# PWR_0V9_20A.net
KiCad netlist of a schematic drawn in Altium Designer
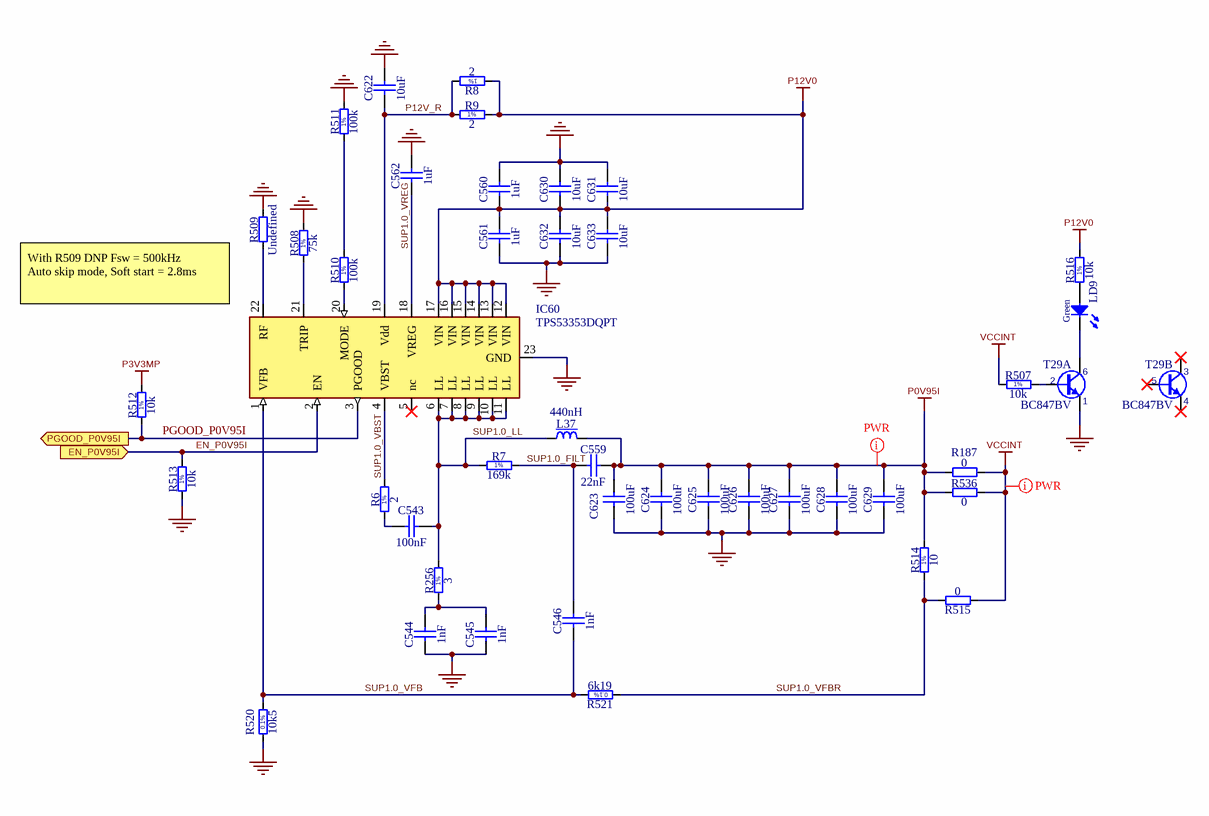
[diagram p0: PWR_0V9_20A.SchDoc]

(export (version "E")
  (design (tool "Eeschema 10.0.6"))
  (components
    (comp (ref "C543")
      (value "100nF")
      (footprint "CAPC1005X55N")
      (description "Non-polarised capacitor")
      (fields
        (field (name "MANUFACTURER PART NUMBER") "CC0402_100NF_16V_10%_X5R")
        (field (name "MANUFACTURER") "GENERIC")
        (field (name "AUTHOR") "CERN DEM JLC")
      )
      (libsource (lib "Capacitors") (part "Capacitor - non polarized"))
    )
    (comp (ref "C544")
      (value "1nF")
      (footprint "CAPC1005X55N")
      (description "Non-polarised capacitor")
      (fields
        (field (name "MANUFACTURER PART NUMBER") "CC0402_1NF_50V_10%_X7R")
        (field (name "MANUFACTURER") "GENERIC")
        (field (name "AUTHOR") "CERN DEM JLC")
      )
      (libsource (lib "Capacitors") (part "Capacitor - non polarized"))
    )
    (comp (ref "C545")
      (value "1nF")
      (footprint "CAPC1005X55N")
      (description "Non-polarised capacitor")
      (fields
        (field (name "MANUFACTURER PART NUMBER") "CC0402_1NF_50V_10%_X7R")
        (field (name "MANUFACTURER") "GENERIC")
        (field (name "AUTHOR") "CERN DEM JLC")
      )
      (libsource (lib "Capacitors") (part "Capacitor - non polarized"))
    )
    (comp (ref "C546")
      (value "1nF")
      (footprint "CAPC1005X55N")
      (description "Non-polarised capacitor")
      (fields
        (field (name "MANUFACTURER PART NUMBER") "CC0402_1NF_50V_10%_X7R")
        (field (name "MANUFACTURER") "GENERIC")
        (field (name "AUTHOR") "CERN DEM JLC")
      )
      (libsource (lib "Capacitors") (part "Capacitor - non polarized"))
    )
    (comp (ref "C559")
      (value "22nF")
      (footprint "CAPC1608X87N")
      (description "Non-polarised capacitor")
      (fields
        (field (name "MANUFACTURER PART NUMBER") "CC0603_22NF_50V_10%_X7R")
        (field (name "MANUFACTURER") "GENERIC")
        (field (name "AUTHOR") "CERN DEM JLC")
      )
      (libsource (lib "Capacitors") (part "Capacitor - non polarized"))
    )
    (comp (ref "C560")
      (value "1uF")
      (footprint "CAPC1608X87N")
      (description "Non-polarised capacitor")
      (fields
        (field (name "MANUFACTURER PART NUMBER") "CC0603_1UF_25V_10%_X7R")
        (field (name "MANUFACTURER") "GENERIC")
        (field (name "AUTHOR") "CERN DEM JLC")
      )
      (libsource (lib "Capacitors") (part "Capacitor - non polarized"))
    )
    (comp (ref "C561")
      (value "1uF")
      (footprint "CAPC1608X87N")
      (description "Non-polarised capacitor")
      (fields
        (field (name "MANUFACTURER PART NUMBER") "CC0603_1UF_25V_10%_X7R")
        (field (name "MANUFACTURER") "GENERIC")
        (field (name "AUTHOR") "CERN DEM JLC")
      )
      (libsource (lib "Capacitors") (part "Capacitor - non polarized"))
    )
    (comp (ref "C562")
      (value "1uF")
      (footprint "CAPC1608X87N")
      (description "Non-polarised capacitor")
      (fields
        (field (name "MANUFACTURER PART NUMBER") "CC0603_1UF_25V_10%_X7R")
        (field (name "MANUFACTURER") "GENERIC")
        (field (name "AUTHOR") "CERN DEM JLC")
      )
      (libsource (lib "Capacitors") (part "Capacitor - non polarized"))
    )
    (comp (ref "C622")
      (value "10uF")
      (footprint "CAPC3216X180N")
      (description "Non-polarised capacitor")
      (fields
        (field (name "MANUFACTURER PART NUMBER") "CC1206_10uF_25V_10%_X7R")
        (field (name "MANUFACTURER") "GENERIC")
        (field (name "AUTHOR") "CERN DEM JLC")
      )
      (libsource (lib "Capacitors") (part "Capacitor - non polarized"))
    )
    (comp (ref "C623")
      (value "100uF")
      (footprint "CAPC3216X180N")
      (description "Non-polarised capacitor")
      (fields
        (field (name "MANUFACTURER PART NUMBER") "CC1206_100UF_6.3V_20%_X5R")
        (field (name "MANUFACTURER") "GENERIC")
        (field (name "AUTHOR") "CERN DEM JLC")
      )
      (libsource (lib "Capacitors") (part "Capacitor - non polarized"))
    )
    (comp (ref "C624")
      (value "100uF")
      (footprint "CAPC3216X180N")
      (description "Non-polarised capacitor")
      (fields
        (field (name "MANUFACTURER PART NUMBER") "CC1206_100UF_6.3V_20%_X5R")
        (field (name "MANUFACTURER") "GENERIC")
        (field (name "AUTHOR") "CERN DEM JLC")
      )
      (libsource (lib "Capacitors") (part "Capacitor - non polarized"))
    )
    (comp (ref "C625")
      (value "100uF")
      (footprint "CAPC3216X180N")
      (description "Non-polarised capacitor")
      (fields
        (field (name "MANUFACTURER PART NUMBER") "CC1206_100UF_6.3V_20%_X5R")
        (field (name "MANUFACTURER") "GENERIC")
        (field (name "AUTHOR") "CERN DEM JLC")
      )
      (libsource (lib "Capacitors") (part "Capacitor - non polarized"))
    )
    (comp (ref "C626")
      (value "100uF")
      (footprint "CAPC3216X180N")
      (description "Non-polarised capacitor")
      (fields
        (field (name "MANUFACTURER PART NUMBER") "CC1206_100UF_6.3V_20%_X5R")
        (field (name "MANUFACTURER") "GENERIC")
        (field (name "AUTHOR") "CERN DEM JLC")
      )
      (libsource (lib "Capacitors") (part "Capacitor - non polarized"))
    )
    (comp (ref "C627")
      (value "100uF")
      (footprint "CAPC3216X180N")
      (description "Non-polarised capacitor")
      (fields
        (field (name "MANUFACTURER PART NUMBER") "CC1206_100UF_6.3V_20%_X5R")
        (field (name "MANUFACTURER") "GENERIC")
        (field (name "AUTHOR") "CERN DEM JLC")
      )
      (libsource (lib "Capacitors") (part "Capacitor - non polarized"))
    )
    (comp (ref "C628")
      (value "100uF")
      (footprint "CAPC3216X180N")
      (description "Non-polarised capacitor")
      (fields
        (field (name "MANUFACTURER PART NUMBER") "CC1206_100UF_6.3V_20%_X5R")
        (field (name "MANUFACTURER") "GENERIC")
        (field (name "AUTHOR") "CERN DEM JLC")
      )
      (libsource (lib "Capacitors") (part "Capacitor - non polarized"))
    )
    (comp (ref "C629")
      (value "100uF")
      (footprint "CAPC3216X180N")
      (description "Non-polarised capacitor")
      (fields
        (field (name "MANUFACTURER PART NUMBER") "CC1206_100UF_6.3V_20%_X5R")
        (field (name "MANUFACTURER") "GENERIC")
        (field (name "AUTHOR") "CERN DEM JLC")
      )
      (libsource (lib "Capacitors") (part "Capacitor - non polarized"))
    )
    (comp (ref "C630")
      (value "10uF")
      (footprint "CAPC3216X180N")
      (description "Non-polarised capacitor")
      (fields
        (field (name "MANUFACTURER PART NUMBER") "CC1206_10uF_25V_10%_X7R")
        (field (name "MANUFACTURER") "GENERIC")
        (field (name "AUTHOR") "CERN DEM JLC")
      )
      (libsource (lib "Capacitors") (part "Capacitor - non polarized"))
    )
    (comp (ref "C631")
      (value "10uF")
      (footprint "CAPC3216X180N")
      (description "Non-polarised capacitor")
      (fields
        (field (name "MANUFACTURER PART NUMBER") "CC1206_10uF_25V_10%_X7R")
        (field (name "MANUFACTURER") "GENERIC")
        (field (name "AUTHOR") "CERN DEM JLC")
      )
      (libsource (lib "Capacitors") (part "Capacitor - non polarized"))
    )
    (comp (ref "C632")
      (value "10uF")
      (footprint "CAPC3216X180N")
      (description "Non-polarised capacitor")
      (fields
        (field (name "MANUFACTURER PART NUMBER") "CC1206_10uF_25V_10%_X7R")
        (field (name "MANUFACTURER") "GENERIC")
        (field (name "AUTHOR") "CERN DEM JLC")
      )
      (libsource (lib "Capacitors") (part "Capacitor - non polarized"))
    )
    (comp (ref "C633")
      (value "10uF")
      (footprint "CAPC3216X180N")
      (description "Non-polarised capacitor")
      (fields
        (field (name "MANUFACTURER PART NUMBER") "CC1206_10uF_25V_10%_X7R")
        (field (name "MANUFACTURER") "GENERIC")
        (field (name "AUTHOR") "CERN DEM JLC")
      )
      (libsource (lib "Capacitors") (part "Capacitor - non polarized"))
    )
    (comp (ref "IC60")
      (value "TPS53353DQPT")
      (footprint "LCCS50P600X500X150-22N")
      (description "High-Efficiency 20-A Synchronous Buck Converter with Eco-mode™")
      (libsource (lib "LIBRARY_SCH") (part "PM_TPS53353"))
    )
    (comp (ref "L37")
      (value "440nH")
      (footprint "IND_PULSE_PA0513")
      (description "Inductor With Core")
      (fields
        (field (name "MANUFACTURER PART NUMBER") "PA0513.441NLT")
        (field (name "MANUFACTURER") "PULSE ELECTRONICS")
        (field (name "AUTHOR") "CERN DEM JLC")
      )
      (libsource (lib "Inductors & Transformers") (part "Inductor With Magnetic core"))
    )
    (comp (ref "LD9")
      (value "Green")
      (footprint "LED_KINGBRIGHT_KPH-1608CGCK")
      (description "LED Green 1C 2A")
      (fields
        (field (name "MANUFACTURER PART NUMBER") "KPH-1608CGCK")
        (field (name "MANUFACTURER") "KINGBRIGHT")
        (field (name "AUTHOR") "CERN DEM JLC")
      )
      (libsource (lib "ICs And Semiconductors") (part "LED Green 1C 2A"))
    )
    (comp (ref "R6")
      (value "2")
      (footprint "RESC1608X55N")
      (description "Resistor - 1%")
      (fields
        (field (name "MANUFACTURER PART NUMBER") "R0603_2R_1%_0.1W_200PPM")
        (field (name "MANUFACTURER") "GENERIC")
        (field (name "AUTHOR") "CERN DEM JLC")
      )
      (libsource (lib "Resistors") (part "Resistor - 1%"))
    )
    (comp (ref "R7")
      (value "169k")
      (footprint "RESC1608X55N")
      (description "Resistor - 1%")
      (fields
        (field (name "MANUFACTURER PART NUMBER") "R0603_169K_1%_0.1W_100PPM")
        (field (name "MANUFACTURER") "GENERIC")
        (field (name "AUTHOR") "CERN DEM JLC")
      )
      (libsource (lib "Resistors") (part "Resistor - 1%"))
    )
    (comp (ref "R8")
      (value "2")
      (footprint "RESC1608X55N")
      (description "Resistor - 1%")
      (fields
        (field (name "MANUFACTURER PART NUMBER") "R0603_2R_1%_0.1W_200PPM")
        (field (name "MANUFACTURER") "GENERIC")
        (field (name "AUTHOR") "CERN DEM JLC")
      )
      (libsource (lib "Resistors") (part "Resistor - 1%"))
    )
    (comp (ref "R9")
      (value "2")
      (footprint "RESC1608X55N")
      (description "Resistor - 1%")
      (fields
        (field (name "MANUFACTURER PART NUMBER") "R0603_2R_1%_0.1W_200PPM")
        (field (name "MANUFACTURER") "GENERIC")
        (field (name "AUTHOR") "CERN DEM JLC")
      )
      (libsource (lib "Resistors") (part "Resistor - 1%"))
    )
    (comp (ref "R187")
      (value "0")
      (footprint "RESC6331X70N")
      (description "Resistor")
      (fields
        (field (name "MANUFACTURER PART NUMBER") "R2512_0R_JUMPER")
        (field (name "MANUFACTURER") "GENERIC")
        (field (name "AUTHOR") "CERN DEM JLC")
      )
      (libsource (lib "Resistors") (part "Resistor"))
    )
    (comp (ref "R256")
      (value "3")
      (footprint "RESC3216X65N")
      (description "Resistor - 1%")
      (fields
        (field (name "MANUFACTURER PART NUMBER") "R1206_3R_1%_0.25W_200PPM")
        (field (name "MANUFACTURER") "GENERIC")
        (field (name "AUTHOR") "CERN DEM JLC")
      )
      (libsource (lib "Resistors") (part "Resistor - 1%"))
    )
    (comp (ref "R507")
      (value "10k")
      (footprint "RESC1005X40N")
      (description "Resistor - 1%")
      (fields
        (field (name "MANUFACTURER PART NUMBER") "R0402_10K_1%_0.0625W_100PPM")
        (field (name "MANUFACTURER") "GENERIC")
        (field (name "AUTHOR") "CERN DEM JLC")
      )
      (libsource (lib "Resistors") (part "Resistor - 1%"))
    )
    (comp (ref "R508")
      (value "75k")
      (footprint "RESC1005X40N")
      (description "Resistor - 1%")
      (fields
        (field (name "MANUFACTURER PART NUMBER") "R0402_75K_1%_0.0625W_100PPM")
        (field (name "MANUFACTURER") "GENERIC")
        (field (name "AUTHOR") "CERN DEM JLC")
      )
      (libsource (lib "Resistors") (part "Resistor - 1%"))
    )
    (comp (ref "R509")
      (value "Undefined")
      (footprint "RESC1005X40N")
      (description "Resistor")
      (fields
        (field (name "MANUFACTURER PART NUMBER") "R0402_NO-VALUE")
        (field (name "AUTHOR") "CERN DEM JLC")
      )
      (libsource (lib "Resistors") (part "Resistor"))
    )
    (comp (ref "R510")
      (value "100k")
      (footprint "RESC1005X40N")
      (description "Resistor - 1%")
      (fields
        (field (name "MANUFACTURER PART NUMBER") "R0402_100K_1%_0.0625W_100PPM")
        (field (name "MANUFACTURER") "GENERIC")
        (field (name "AUTHOR") "CERN DEM JLC")
      )
      (libsource (lib "Resistors") (part "Resistor - 1%"))
    )
    (comp (ref "R511")
      (value "100k")
      (footprint "RESC1005X40N")
      (description "Resistor - 1%")
      (fields
        (field (name "MANUFACTURER PART NUMBER") "R0402_100K_1%_0.0625W_100PPM")
        (field (name "MANUFACTURER") "GENERIC")
        (field (name "AUTHOR") "CERN DEM JLC")
      )
      (libsource (lib "Resistors") (part "Resistor - 1%"))
    )
    (comp (ref "R512")
      (value "10k")
      (footprint "RESC1005X40N")
      (description "Resistor - 1%")
      (fields
        (field (name "MANUFACTURER PART NUMBER") "R0402_10K_1%_0.0625W_100PPM")
        (field (name "MANUFACTURER") "GENERIC")
        (field (name "AUTHOR") "CERN DEM JLC")
      )
      (libsource (lib "Resistors") (part "Resistor - 1%"))
    )
    (comp (ref "R513")
      (value "10k")
      (footprint "RESC1005X40N")
      (description "Resistor - 1%")
      (fields
        (field (name "MANUFACTURER PART NUMBER") "R0402_10K_1%_0.0625W_100PPM")
        (field (name "MANUFACTURER") "GENERIC")
        (field (name "AUTHOR") "CERN DEM JLC")
      )
      (libsource (lib "Resistors") (part "Resistor - 1%"))
    )
    (comp (ref "R514")
      (value "10")
      (footprint "RESC1005X40N")
      (description "Resistor - 1%")
      (fields
        (field (name "MANUFACTURER PART NUMBER") "R0402_10R_1%_0.0625W_200PPM")
        (field (name "MANUFACTURER") "GENERIC")
        (field (name "AUTHOR") "CERN DEM JLC")
      )
      (libsource (lib "Resistors") (part "Resistor - 1%"))
    )
    (comp (ref "R515")
      (value "0")
      (footprint "RESC1005X40N")
      (description "Resistor")
      (fields
        (field (name "MANUFACTURER PART NUMBER") "R0402_0R_JUMPER")
        (field (name "MANUFACTURER") "GENERIC")
        (field (name "AUTHOR") "CERN DEM JLC")
      )
      (libsource (lib "Resistors") (part "Resistor"))
    )
    (comp (ref "R516")
      (value "10k")
      (footprint "RESC1005X40N")
      (description "Resistor - 1%")
      (fields
        (field (name "MANUFACTURER PART NUMBER") "R0402_10K_1%_0.0625W_100PPM")
        (field (name "MANUFACTURER") "GENERIC")
        (field (name "AUTHOR") "CERN DEM JLC")
      )
      (libsource (lib "Resistors") (part "Resistor - 1%"))
    )
    (comp (ref "R520")
      (value "10k5")
      (footprint "RESC1608X55N")
      (description "Resistor - 0.1%")
      (fields
        (field (name "MANUFACTURER PART NUMBER") "R0603_10K5_0.1%_0.063W_10PPM")
        (field (name "MANUFACTURER") "GENERIC")
        (field (name "AUTHOR") "CERN DEM JLC")
      )
      (libsource (lib "Resistors") (part "Resistor - 0.1%"))
    )
    (comp (ref "R521")
      (value "6k19")
      (footprint "RESC1608X55N")
      (description "Resistor - 0.1%")
      (fields
        (field (name "MANUFACTURER PART NUMBER") "R0603_6K19_0.1%_0.063W_10PPM")
        (field (name "MANUFACTURER") "GENERIC")
        (field (name "AUTHOR") "CERN DEM JLC")
      )
      (libsource (lib "Resistors") (part "Resistor - 0.1%"))
    )
    (comp (ref "R536")
      (value "0")
      (footprint "RESC6331X70N")
      (description "Resistor")
      (fields
        (field (name "MANUFACTURER PART NUMBER") "R2512_0R_JUMPER")
        (field (name "MANUFACTURER") "GENERIC")
        (field (name "AUTHOR") "CERN DEM JLC")
      )
      (libsource (lib "Resistors") (part "Resistor"))
    )
    (comp (ref "T29")
      (value "BC847BV")
      (footprint "SOTFL50P160X60-6N")
      (description "45V, 100mA NPN General Purpose Double Transistor")
      (fields (field (name "MANUFACTURER") "NXP SEMICONDUCTORS") (field (name "AUTHOR") "CERN DEM JLC"))
      (libsource (lib "ICs And Semiconductors") (part "BC847BV"))
    )
  )
  (nets
    (net (code "1") (name "/EN_P0V95I") (class "Default")
      (node (ref "IC60") (pin "2") (pinfunction "EN_2") (pintype "input"))
      (node (ref "R513") (pin "2") (pinfunction "2_2") (pintype "passive"))
    )
    (net (code "2") (name "/P12V_R") (class "Default")
      (node (ref "C622") (pin "1") (pinfunction "1_1") (pintype "passive"))
      (node (ref "IC60") (pin "19") (pinfunction "Vdd_19") (pintype "power_in"))
      (node (ref "R8") (pin "1") (pinfunction "1_1") (pintype "passive"))
      (node (ref "R9") (pin "1") (pinfunction "1_1") (pintype "passive"))
    )
    (net (code "3") (name "/PGOOD_P0V95I") (class "Default")
      (node (ref "IC60") (pin "3") (pinfunction "PGOOD_3") (pintype "output"))
      (node (ref "R512") (pin "1") (pinfunction "1_1") (pintype "passive"))
    )
    (net (code "4") (name "/SUP1.0_FILT") (class "Default")
      (node (ref "C546") (pin "2") (pinfunction "2_2") (pintype "passive"))
      (node (ref "C559") (pin "1") (pinfunction "1_1") (pintype "passive"))
      (node (ref "R7") (pin "2") (pinfunction "2_2") (pintype "passive"))
    )
    (net (code "5") (name "/SUP1.0_LL") (class "Default")
      (node (ref "C543") (pin "2") (pinfunction "2_2") (pintype "passive"))
      (node (ref "IC60") (pin "10") (pinfunction "LL_10") (pintype "passive"))
      (node (ref "IC60") (pin "11") (pinfunction "LL_11") (pintype "passive"))
      (node (ref "IC60") (pin "6") (pinfunction "LL_6") (pintype "passive"))
      (node (ref "IC60") (pin "7") (pinfunction "LL_7") (pintype "passive"))
      (node (ref "IC60") (pin "8") (pinfunction "LL_8") (pintype "passive"))
      (node (ref "IC60") (pin "9") (pinfunction "LL_9") (pintype "passive"))
      (node (ref "L37") (pin "1") (pinfunction "1_1") (pintype "passive"))
      (node (ref "R256") (pin "2") (pinfunction "2_2") (pintype "passive"))
      (node (ref "R7") (pin "1") (pinfunction "1_1") (pintype "passive"))
    )
    (net (code "6") (name "/SUP1.0_VBST") (class "Default")
      (node (ref "IC60") (pin "4") (pinfunction "VBST_4") (pintype "passive"))
      (node (ref "R6") (pin "2") (pinfunction "2_2") (pintype "passive"))
    )
    (net (code "7") (name "/SUP1.0_VFB") (class "Default")
      (node (ref "C546") (pin "1") (pinfunction "1_1") (pintype "passive"))
      (node (ref "IC60") (pin "1") (pinfunction "VFB_1") (pintype "input"))
      (node (ref "R520") (pin "2") (pinfunction "2_2") (pintype "passive"))
      (node (ref "R521") (pin "2") (pinfunction "2_2") (pintype "passive"))
    )
    (net (code "8") (name "/SUP1.0_VFBR") (class "Default")
      (node (ref "R514") (pin "1") (pinfunction "1_1") (pintype "passive"))
      (node (ref "R515") (pin "2") (pinfunction "2_2") (pintype "passive"))
      (node (ref "R521") (pin "1") (pinfunction "1_1") (pintype "passive"))
    )
    (net (code "9") (name "/SUP1.0_VREG") (class "Default")
      (node (ref "C562") (pin "1") (pinfunction "1_1") (pintype "passive"))
      (node (ref "IC60") (pin "18") (pinfunction "VREG_18") (pintype "power_in"))
    )
    (net (code "10") (name "GND") (class "Default")
      (node (ref "C544") (pin "1") (pinfunction "1_1") (pintype "passive"))
      (node (ref "C545") (pin "1") (pinfunction "1_1") (pintype "passive"))
      (node (ref "C560") (pin "2") (pinfunction "2_2") (pintype "passive"))
      (node (ref "C561") (pin "1") (pinfunction "1_1") (pintype "passive"))
      (node (ref "C562") (pin "2") (pinfunction "2_2") (pintype "passive"))
      (node (ref "C622") (pin "2") (pinfunction "2_2") (pintype "passive"))
      (node (ref "C623") (pin "1") (pinfunction "1_1") (pintype "passive"))
      (node (ref "C624") (pin "1") (pinfunction "1_1") (pintype "passive"))
      (node (ref "C625") (pin "1") (pinfunction "1_1") (pintype "passive"))
      (node (ref "C626") (pin "1") (pinfunction "1_1") (pintype "passive"))
      (node (ref "C627") (pin "1") (pinfunction "1_1") (pintype "passive"))
      (node (ref "C628") (pin "1") (pinfunction "1_1") (pintype "passive"))
      (node (ref "C629") (pin "1") (pinfunction "1_1") (pintype "passive"))
      (node (ref "C630") (pin "2") (pinfunction "2_2") (pintype "passive"))
      (node (ref "C631") (pin "2") (pinfunction "2_2") (pintype "passive"))
      (node (ref "C632") (pin "1") (pinfunction "1_1") (pintype "passive"))
      (node (ref "C633") (pin "1") (pinfunction "1_1") (pintype "passive"))
      (node (ref "IC60") (pin "23") (pinfunction "GND_23") (pintype "power_in"))
      (node (ref "R508") (pin "2") (pinfunction "2_2") (pintype "passive"))
      (node (ref "R509") (pin "2") (pinfunction "2_2") (pintype "passive"))
      (node (ref "R511") (pin "2") (pinfunction "2_2") (pintype "passive"))
      (node (ref "R513") (pin "1") (pinfunction "1_1") (pintype "passive"))
      (node (ref "R520") (pin "1") (pinfunction "1_1") (pintype "passive"))
      (node (ref "T29") (pin "1") (pinfunction "E_1") (pintype "passive"))
    )
    (net (code "11") (name "Net-(C543-Pad1)") (class "Default")
      (node (ref "C543") (pin "1") (pinfunction "1_1") (pintype "passive"))
      (node (ref "R6") (pin "1") (pinfunction "1_1") (pintype "passive"))
    )
    (net (code "12") (name "Net-(C544-Pad2)") (class "Default")
      (node (ref "C544") (pin "2") (pinfunction "2_2") (pintype "passive"))
      (node (ref "C545") (pin "2") (pinfunction "2_2") (pintype "passive"))
      (node (ref "R256") (pin "1") (pinfunction "1_1") (pintype "passive"))
    )
    (net (code "13") (name "Net-(IC60-MODE)") (class "Default")
      (node (ref "IC60") (pin "20") (pinfunction "MODE_20") (pintype "input"))
      (node (ref "R510") (pin "1") (pinfunction "1_1") (pintype "passive"))
    )
    (net (code "14") (name "Net-(IC60-RF)") (class "Default")
      (node (ref "IC60") (pin "22") (pinfunction "RF_22") (pintype "passive"))
      (node (ref "R509") (pin "1") (pinfunction "1_1") (pintype "passive"))
    )
    (net (code "15") (name "Net-(IC60-TRIP)") (class "Default")
      (node (ref "IC60") (pin "21") (pinfunction "TRIP_21") (pintype "passive"))
      (node (ref "R508") (pin "1") (pinfunction "1_1") (pintype "passive"))
    )
    (net (code "16") (name "Net-(LD9-A)") (class "Default")
      (node (ref "LD9") (pin "2") (pinfunction "A_2") (pintype "passive"))
      (node (ref "R516") (pin "1") (pinfunction "1_1") (pintype "passive"))
    )
    (net (code "17") (name "Net-(LD9-C)") (class "Default")
      (node (ref "LD9") (pin "1") (pinfunction "C_1") (pintype "passive"))
      (node (ref "T29") (pin "6") (pinfunction "C_6") (pintype "passive"))
    )
    (net (code "18") (name "Net-(R510-Pad2)") (class "Default")
      (node (ref "R510") (pin "2") (pinfunction "2_2") (pintype "passive"))
      (node (ref "R511") (pin "1") (pinfunction "1_1") (pintype "passive"))
    )
    (net (code "19") (name "Net-(T29A-B)") (class "Default")
      (node (ref "R507") (pin "2") (pinfunction "2_2") (pintype "passive"))
      (node (ref "T29") (pin "2") (pinfunction "B_2") (pintype "passive"))
    )
    (net (code "20") (name "P0V95I") (class "Default")
      (node (ref "C559") (pin "2") (pinfunction "2_2") (pintype "passive"))
      (node (ref "C623") (pin "2") (pinfunction "2_2") (pintype "passive"))
      (node (ref "C624") (pin "2") (pinfunction "2_2") (pintype "passive"))
      (node (ref "C625") (pin "2") (pinfunction "2_2") (pintype "passive"))
      (node (ref "C626") (pin "2") (pinfunction "2_2") (pintype "passive"))
      (node (ref "C627") (pin "2") (pinfunction "2_2") (pintype "passive"))
      (node (ref "C628") (pin "2") (pinfunction "2_2") (pintype "passive"))
      (node (ref "C629") (pin "2") (pinfunction "2_2") (pintype "passive"))
      (node (ref "L37") (pin "2") (pinfunction "2_2") (pintype "passive"))
      (node (ref "R187") (pin "1") (pinfunction "1_1") (pintype "passive"))
      (node (ref "R514") (pin "2") (pinfunction "2_2") (pintype "passive"))
      (node (ref "R536") (pin "1") (pinfunction "1_1") (pintype "passive"))
    )
    (net (code "21") (name "P3V3MP") (class "Default")
      (node (ref "R512") (pin "2") (pinfunction "2_2") (pintype "passive"))
    )
    (net (code "22") (name "P12V0") (class "Default")
      (node (ref "C560") (pin "1") (pinfunction "1_1") (pintype "passive"))
      (node (ref "C561") (pin "2") (pinfunction "2_2") (pintype "passive"))
      (node (ref "C630") (pin "1") (pinfunction "1_1") (pintype "passive"))
      (node (ref "C631") (pin "1") (pinfunction "1_1") (pintype "passive"))
      (node (ref "C632") (pin "2") (pinfunction "2_2") (pintype "passive"))
      (node (ref "C633") (pin "2") (pinfunction "2_2") (pintype "passive"))
      (node (ref "IC60") (pin "12") (pinfunction "VIN_12") (pintype "power_in"))
      (node (ref "IC60") (pin "13") (pinfunction "VIN_13") (pintype "power_in"))
      (node (ref "IC60") (pin "14") (pinfunction "VIN_14") (pintype "power_in"))
      (node (ref "IC60") (pin "15") (pinfunction "VIN_15") (pintype "power_in"))
      (node (ref "IC60") (pin "16") (pinfunction "VIN_16") (pintype "power_in"))
      (node (ref "IC60") (pin "17") (pinfunction "VIN_17") (pintype "power_in"))
      (node (ref "R516") (pin "2") (pinfunction "2_2") (pintype "passive"))
      (node (ref "R8") (pin "2") (pinfunction "2_2") (pintype "passive"))
      (node (ref "R9") (pin "2") (pinfunction "2_2") (pintype "passive"))
    )
    (net (code "23") (name "VCCINT") (class "Default")
      (node (ref "R187") (pin "2") (pinfunction "2_2") (pintype "passive"))
      (node (ref "R507") (pin "1") (pinfunction "1_1") (pintype "passive"))
      (node (ref "R515") (pin "1") (pinfunction "1_1") (pintype "passive"))
      (node (ref "R536") (pin "2") (pinfunction "2_2") (pintype "passive"))
    )
    (net (code "24") (name "unconnected-(IC60-nc-Pad5)") (class "Default")
      (node (ref "IC60") (pin "5") (pinfunction "nc_5") (pintype "passive+no_connect"))
    )
    (net (code "25") (name "unconnected-(T29B-B-Pad5)") (class "Default")
      (node (ref "T29") (pin "5") (pinfunction "B_5") (pintype "passive+no_connect"))
    )
    (net (code "26") (name "unconnected-(T29B-C-Pad3)") (class "Default")
      (node (ref "T29") (pin "3") (pinfunction "C_3") (pintype "passive+no_connect"))
    )
    (net (code "27") (name "unconnected-(T29B-E-Pad4)") (class "Default")
      (node (ref "T29") (pin "4") (pinfunction "E_4") (pintype "passive+no_connect"))
    )
  )
)
